# MB1297_NFC_SAFE.net
KiCad netlist of a schematic drawn in Altium Designer
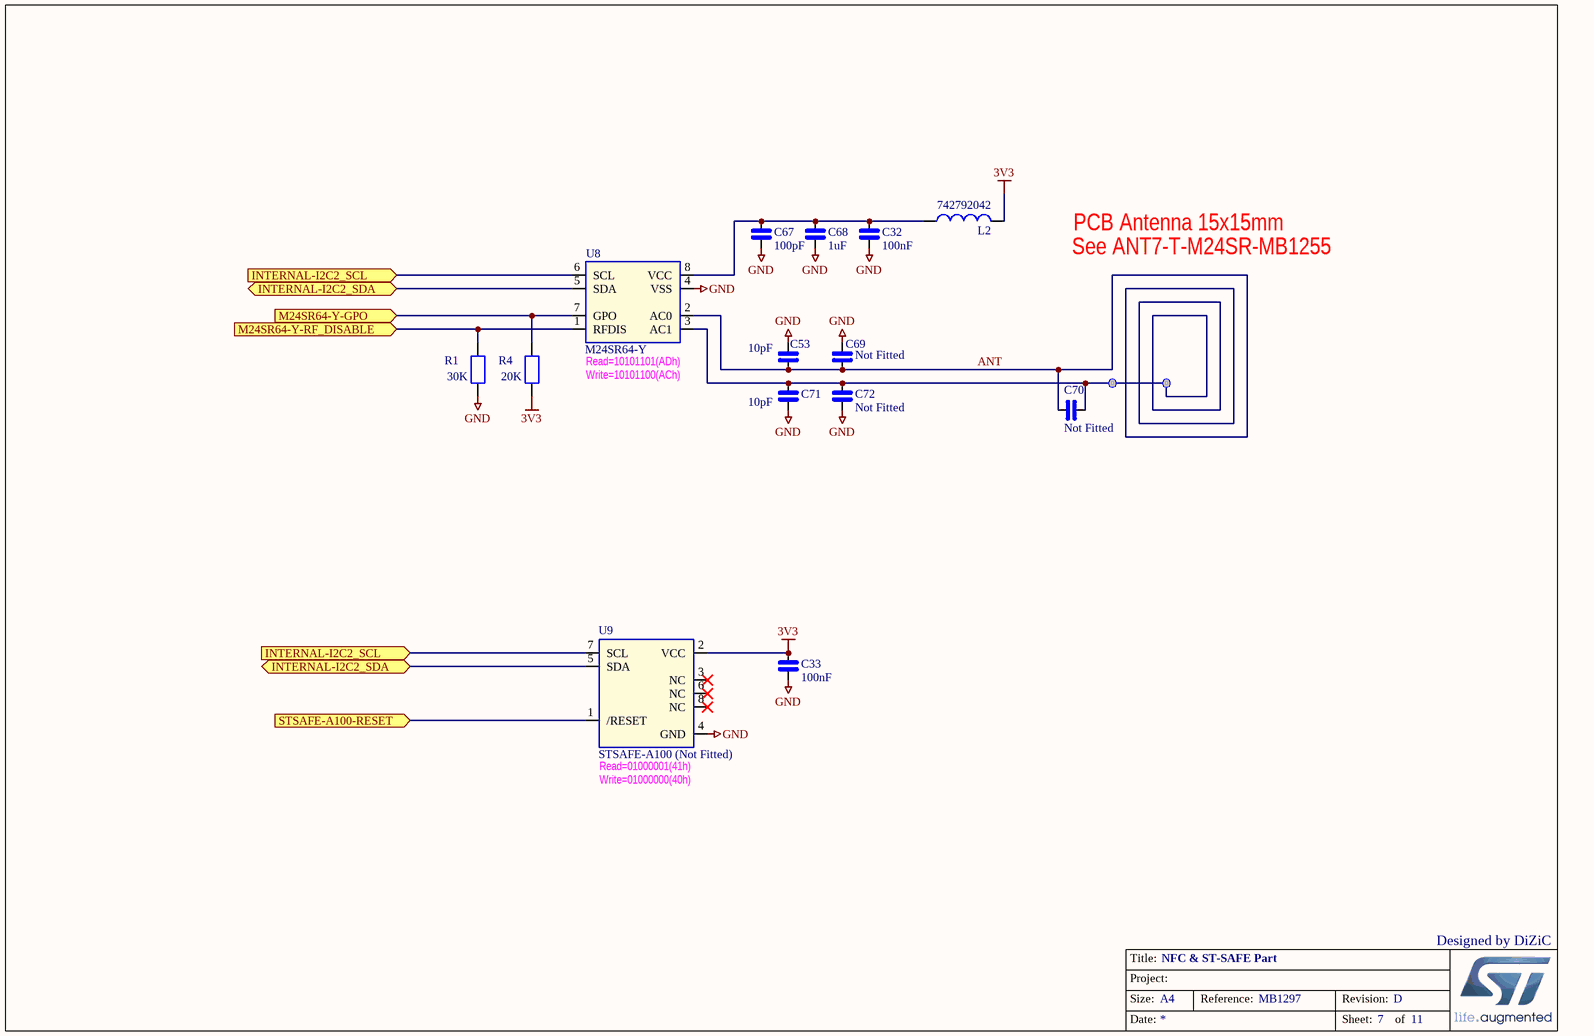
[diagram p0: MB1297_NFC_SAFE.SchDoc]

(export (version "E")
  (design (tool "Eeschema 10.0.6"))
  (components
    (comp (ref "C32")
      (value "100nF")
      (footprint "0402_CAP_NPOL")
      (description "Capacitor_not polarized")
      (libsource (lib "ST_Lib3D") (part "CAP_NPOL"))
    )
    (comp (ref "C33")
      (value "100nF")
      (footprint "0402_CAP_NPOL")
      (description "Capacitor_not polarized")
      (libsource (lib "ST_Lib3D") (part "CAP_NPOL"))
    )
    (comp (ref "C53")
      (value "10pF")
      (footprint "0402_CAP_NPOL")
      (description "Capacitor_not polarized")
      (libsource (lib "ST_Lib3D") (part "CAP_NPOL"))
    )
    (comp (ref "C67")
      (value "100pF")
      (footprint "0402_CAP_NPOL")
      (description "Capacitor_not polarized")
      (libsource (lib "ST_Lib3D") (part "CAP_NPOL"))
    )
    (comp (ref "C68")
      (value "1uF")
      (footprint "0402_CAP_NPOL")
      (description "Capacitor_not polarized")
      (libsource (lib "ST_Lib3D") (part "CAP_NPOL"))
    )
    (comp (ref "C69")
      (value "Not Fitted")
      (footprint "0402_CAP_NPOL")
      (description "Capacitor_not polarized")
      (libsource (lib "ST_Lib3D") (part "CAP_NPOL"))
    )
    (comp (ref "C70")
      (value "Not Fitted")
      (footprint "0402_CAP_NPOL")
      (description "Capacitor_not polarized")
      (libsource (lib "ST_Lib3D") (part "CAP_NPOL"))
    )
    (comp (ref "C71")
      (value "10pF")
      (footprint "0402_CAP_NPOL")
      (description "Capacitor_not polarized")
      (libsource (lib "ST_Lib3D") (part "CAP_NPOL"))
    )
    (comp (ref "C72")
      (value "Not Fitted")
      (footprint "0402_CAP_NPOL")
      (description "Capacitor_not polarized")
      (libsource (lib "ST_Lib3D") (part "CAP_NPOL"))
    )
    (comp (ref "L2")
      (value "742792042")
      (footprint "0603L")
      (description "Inductor")
      (fields (field (name "PUBLISHER") "Altium Limited"))
      (libsource (lib "Miscellaneous Devices") (part "Inductor"))
    )
    (comp (ref "R1")
      (value "30K")
      (footprint "0402_RES")
      (description "Resistor")
      (libsource (lib "ST_Lib3D") (part "RES"))
    )
    (comp (ref "R4")
      (value "20K")
      (footprint "0402_RES")
      (description "Resistor")
      (libsource (lib "ST_Lib3D") (part "RES"))
    )
    (comp (ref "U8")
      (value "M24SR64-Y")
      (footprint "SOP8")
      (description "M24SR64-Y  64K_EEPROM NFC/RFID")
      (libsource (lib "ST_Lib3D") (part "M24SR64-Y"))
    )
    (comp (ref "U9")
      (value "STSAFE-A100 (Not Fitted)")
      (footprint "SOP8")
      (description "STSAFE-A100")
      (libsource (lib "ST_Lib3D") (part "STSAFE-A100"))
    )
  )
  (nets
    (net (code "1") (name "/ANT") (class "Default")
      (node (ref "C53") (pin "1") (pinfunction "1_1") (pintype "passive"))
      (node (ref "C69") (pin "1") (pinfunction "1_1") (pintype "passive"))
      (node (ref "C70") (pin "1") (pinfunction "1_1") (pintype "passive"))
      (node (ref "C70") (pin "2") (pinfunction "2_2") (pintype "passive"))
      (node (ref "C71") (pin "1") (pinfunction "1_1") (pintype "passive"))
      (node (ref "C72") (pin "1") (pinfunction "1_1") (pintype "passive"))
      (node (ref "U8") (pin "2") (pinfunction "AC0_2") (pintype "passive"))
      (node (ref "U8") (pin "3") (pinfunction "AC1_3") (pintype "passive"))
    )
    (net (code "2") (name "/INTERNAL-I2C2_SCL") (class "Default")
      (node (ref "U8") (pin "6") (pinfunction "SCL_6") (pintype "passive"))
      (node (ref "U9") (pin "7") (pinfunction "SCL_7") (pintype "passive"))
    )
    (net (code "3") (name "/INTERNAL-I2C2_SDA") (class "Default")
      (node (ref "U8") (pin "5") (pinfunction "SDA_5") (pintype "passive"))
      (node (ref "U9") (pin "5") (pinfunction "SDA_5") (pintype "passive"))
    )
    (net (code "4") (name "/M24SR64-Y-GPO") (class "Default")
      (node (ref "R4") (pin "2") (pinfunction "2_2") (pintype "passive"))
      (node (ref "U8") (pin "7") (pinfunction "GPO_7") (pintype "passive"))
    )
    (net (code "5") (name "/M24SR64-Y-RF_DISABLE") (class "Default")
      (node (ref "R1") (pin "2") (pinfunction "2_2") (pintype "passive"))
      (node (ref "U8") (pin "1") (pinfunction "RFDIS_1") (pintype "passive"))
    )
    (net (code "6") (name "/STSAFE-A100-RESET") (class "Default")
      (node (ref "U9") (pin "1") (pinfunction "/RESET_1") (pintype "passive"))
    )
    (net (code "7") (name "3V3") (class "Default")
      (node (ref "C33") (pin "1") (pinfunction "1_1") (pintype "passive"))
      (node (ref "L2") (pin "2") (pinfunction "2_2") (pintype "passive"))
      (node (ref "R4") (pin "1") (pinfunction "1_1") (pintype "passive"))
      (node (ref "U9") (pin "2") (pinfunction "VCC_2") (pintype "passive"))
    )
    (net (code "8") (name "GND") (class "Default")
      (node (ref "C32") (pin "2") (pinfunction "2_2") (pintype "passive"))
      (node (ref "C33") (pin "2") (pinfunction "2_2") (pintype "passive"))
      (node (ref "C53") (pin "2") (pinfunction "2_2") (pintype "passive"))
      (node (ref "C67") (pin "2") (pinfunction "2_2") (pintype "passive"))
      (node (ref "C68") (pin "2") (pinfunction "2_2") (pintype "passive"))
      (node (ref "C69") (pin "2") (pinfunction "2_2") (pintype "passive"))
      (node (ref "C71") (pin "2") (pinfunction "2_2") (pintype "passive"))
      (node (ref "C72") (pin "2") (pinfunction "2_2") (pintype "passive"))
      (node (ref "R1") (pin "1") (pinfunction "1_1") (pintype "passive"))
      (node (ref "U8") (pin "4") (pinfunction "VSS_4") (pintype "passive"))
      (node (ref "U9") (pin "4") (pinfunction "GND_4") (pintype "passive"))
    )
    (net (code "9") (name "Net-(U8-VCC)") (class "Default")
      (node (ref "C32") (pin "1") (pinfunction "1_1") (pintype "passive"))
      (node (ref "C67") (pin "1") (pinfunction "1_1") (pintype "passive"))
      (node (ref "C68") (pin "1") (pinfunction "1_1") (pintype "passive"))
      (node (ref "L2") (pin "1") (pinfunction "1_1") (pintype "passive"))
      (node (ref "U8") (pin "8") (pinfunction "VCC_8") (pintype "passive"))
    )
    (net (code "10") (name "unconnected-(U9-NC-Pad3)") (class "Default")
      (node (ref "U9") (pin "3") (pinfunction "NC_3") (pintype "passive+no_connect"))
    )
    (net (code "11") (name "unconnected-(U9-NC-Pad6)") (class "Default")
      (node (ref "U9") (pin "6") (pinfunction "NC_6") (pintype "passive+no_connect"))
    )
    (net (code "12") (name "unconnected-(U9-NC-Pad8)") (class "Default")
      (node (ref "U9") (pin "8") (pinfunction "NC_8") (pintype "passive+no_connect"))
    )
  )
)
